# NodeMCUDisplayShield.net
KiCad netlist of a schematic drawn in EAGLE
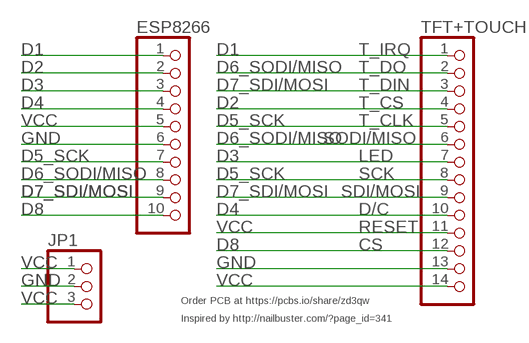
[diagram p0: schematic, sheet 1]

(export (version "E")
  (design (tool "Eeschema 10.0.6"))
  (components
    (comp (ref "ESP8266")
      (value "PINHD-1X10/OCT")
      (footprint "eagle-import:1X10_OCT")
      (libsource (lib "eagle-import") (part "PINHD-1X10/OCT"))
    )
    (comp (ref "JP1")
      (value "PINHD-1X3/OCT")
      (footprint "eagle-import:1X03_OCT")
      (libsource (lib "eagle-import") (part "PINHD-1X3/OCT"))
    )
    (comp (ref "TFT+TOUCH")
      (value "PINHD-1X14/OCT")
      (footprint "eagle-import:1X14_OCT")
      (libsource (lib "eagle-import") (part "PINHD-1X14/OCT"))
    )
  )
  (nets
    (net (code "1") (name "/D1") (class "Default")
      (node (ref "ESP8266") (pin "1") (pinfunction "1_1") (pintype "passive"))
      (node (ref "TFT+TOUCH") (pin "1") (pinfunction "1_1") (pintype "passive"))
    )
    (net (code "2") (name "/D2") (class "Default")
      (node (ref "ESP8266") (pin "2") (pinfunction "2_2") (pintype "passive"))
      (node (ref "TFT+TOUCH") (pin "4") (pinfunction "4_4") (pintype "passive"))
    )
    (net (code "3") (name "/D3") (class "Default")
      (node (ref "ESP8266") (pin "3") (pinfunction "3_3") (pintype "passive"))
      (node (ref "TFT+TOUCH") (pin "7") (pinfunction "7_7") (pintype "passive"))
    )
    (net (code "4") (name "/D4") (class "Default")
      (node (ref "ESP8266") (pin "4") (pinfunction "4_4") (pintype "passive"))
      (node (ref "TFT+TOUCH") (pin "10") (pinfunction "10_10") (pintype "passive"))
    )
    (net (code "5") (name "/D5_SCK") (class "Default")
      (node (ref "ESP8266") (pin "7") (pinfunction "7_7") (pintype "passive"))
      (node (ref "TFT+TOUCH") (pin "5") (pinfunction "5_5") (pintype "passive"))
      (node (ref "TFT+TOUCH") (pin "8") (pinfunction "8_8") (pintype "passive"))
    )
    (net (code "6") (name "/D6_SODI{slash}MISO") (class "Default")
      (node (ref "ESP8266") (pin "8") (pinfunction "8_8") (pintype "passive"))
      (node (ref "TFT+TOUCH") (pin "2") (pinfunction "2_2") (pintype "passive"))
      (node (ref "TFT+TOUCH") (pin "6") (pinfunction "6_6") (pintype "passive"))
    )
    (net (code "7") (name "/D7_SDI{slash}MOSI") (class "Default")
      (node (ref "ESP8266") (pin "9") (pinfunction "9_9") (pintype "passive"))
      (node (ref "TFT+TOUCH") (pin "3") (pinfunction "3_3") (pintype "passive"))
      (node (ref "TFT+TOUCH") (pin "9") (pinfunction "9_9") (pintype "passive"))
    )
    (net (code "8") (name "/D8") (class "Default")
      (node (ref "ESP8266") (pin "10") (pinfunction "10_10") (pintype "passive"))
      (node (ref "TFT+TOUCH") (pin "12") (pinfunction "12_12") (pintype "passive"))
    )
    (net (code "9") (name "/GND") (class "Default")
      (node (ref "ESP8266") (pin "6") (pinfunction "6_6") (pintype "passive"))
      (node (ref "JP1") (pin "2") (pinfunction "2_2") (pintype "passive"))
      (node (ref "TFT+TOUCH") (pin "13") (pinfunction "13_13") (pintype "passive"))
    )
    (net (code "10") (name "/VCC") (class "Default")
      (node (ref "ESP8266") (pin "5") (pinfunction "5_5") (pintype "passive"))
      (node (ref "JP1") (pin "1") (pinfunction "1_1") (pintype "passive"))
      (node (ref "JP1") (pin "3") (pinfunction "3_3") (pintype "passive"))
      (node (ref "TFT+TOUCH") (pin "11") (pinfunction "11_11") (pintype "passive"))
      (node (ref "TFT+TOUCH") (pin "14") (pinfunction "14_14") (pintype "passive"))
    )
  )
)
